# 395_Smartwatch.net
KiCad netlist of a schematic drawn in EAGLE
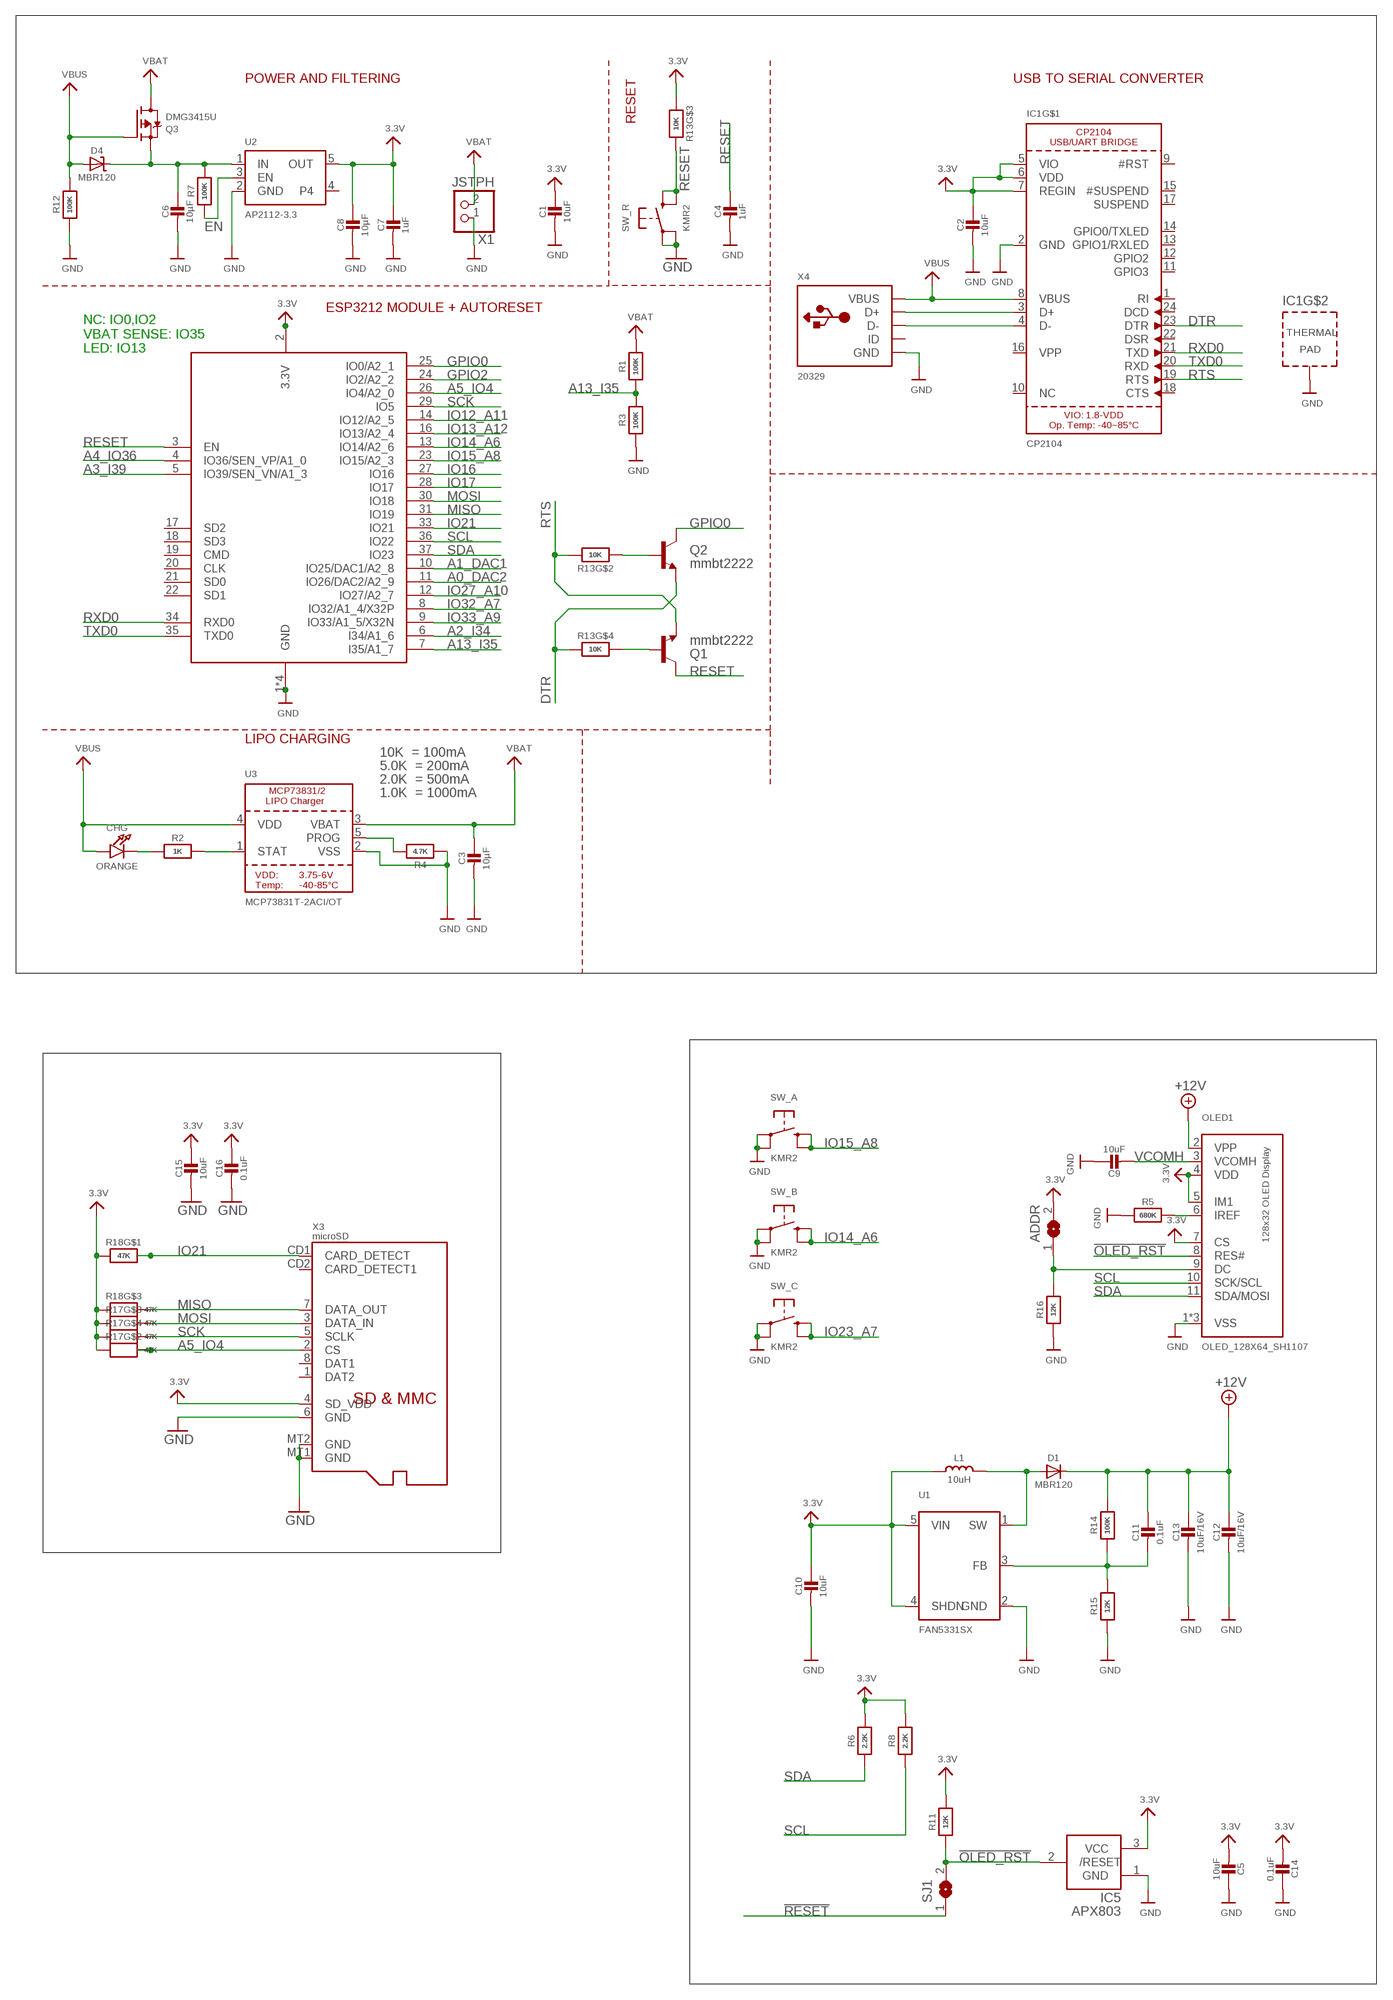
[diagram p0: schematic, sheet 1]

(export (version "E")
  (design (tool "Eeschema 10.0.6"))
  (components
    (comp (ref "ADDR")
      (value "SOLDERJUMPER")
      (footprint "eagle-import:SOLDERJUMPER_ARROW_NOPASTE")
      (libsource (lib "eagle-import") (part "SOLDERJUMPER"))
    )
    (comp (ref "C1")
      (value "10uF")
      (footprint "eagle-import:0805-NO")
      (libsource (lib "eagle-import") (part "CAP_CERAMIC0805-NOOUTLINE"))
    )
    (comp (ref "C2")
      (value "10uF")
      (footprint "eagle-import:0805-NO")
      (libsource (lib "eagle-import") (part "CAP_CERAMIC0805-NOOUTLINE"))
    )
    (comp (ref "C3")
      (value "10µF")
      (footprint "eagle-import:0805-NO")
      (libsource (lib "eagle-import") (part "CAP_CERAMIC0805-NOOUTLINE"))
    )
    (comp (ref "C4")
      (value "1uF")
      (footprint "eagle-import:0603-NO")
      (libsource (lib "eagle-import") (part "CAP_CERAMIC0603_NO"))
    )
    (comp (ref "C5")
      (value "10uF")
      (footprint "eagle-import:0805-NO")
      (libsource (lib "eagle-import") (part "CAP_CERAMIC0805-NOOUTLINE"))
    )
    (comp (ref "C6")
      (value "10µF")
      (footprint "eagle-import:0805-NO")
      (libsource (lib "eagle-import") (part "CAP_CERAMIC0805-NOOUTLINE"))
    )
    (comp (ref "C7")
      (value "1uF")
      (footprint "eagle-import:0603-NO")
      (libsource (lib "eagle-import") (part "CAP_CERAMIC0603_NO"))
    )
    (comp (ref "C8")
      (value "10µF")
      (footprint "eagle-import:0805-NO")
      (libsource (lib "eagle-import") (part "CAP_CERAMIC0805-NOOUTLINE"))
    )
    (comp (ref "C9")
      (value "10uF")
      (footprint "eagle-import:0805-NO")
      (libsource (lib "eagle-import") (part "CAP_CERAMIC0805-NOOUTLINE"))
    )
    (comp (ref "C10")
      (value "10uF")
      (footprint "eagle-import:0805-NO")
      (libsource (lib "eagle-import") (part "CAP_CERAMIC0805-NOOUTLINE"))
    )
    (comp (ref "C11")
      (value "0.1uF")
      (footprint "eagle-import:0603-NO")
      (libsource (lib "eagle-import") (part "CAP_CERAMIC0603_NO"))
    )
    (comp (ref "C12")
      (value "10uF/16V")
      (footprint "eagle-import:0805-NO")
      (libsource (lib "eagle-import") (part "CAP_CERAMIC0805-NOOUTLINE"))
    )
    (comp (ref "C13")
      (value "10uF/16V")
      (footprint "eagle-import:0805-NO")
      (libsource (lib "eagle-import") (part "CAP_CERAMIC0805-NOOUTLINE"))
    )
    (comp (ref "C14")
      (value "0.1uF")
      (footprint "eagle-import:0603-NO")
      (libsource (lib "eagle-import") (part "CAP_CERAMIC0603_NO"))
    )
    (comp (ref "C15")
      (value "10uF")
      (footprint "eagle-import:0805-NO")
      (libsource (lib "eagle-import") (part "CAP_CERAMIC0805-NOOUTLINE"))
    )
    (comp (ref "C16")
      (value "0.1uF")
      (footprint "eagle-import:0603-NO")
      (libsource (lib "eagle-import") (part "CAP_CERAMIC0603_NO"))
    )
    (comp (ref "CHG")
      (value "ORANGE")
      (footprint "eagle-import:CHIPLED_0805_NOOUTLINE")
      (libsource (lib "eagle-import") (part "LED0805_NOOUTLINE"))
    )
    (comp (ref "D1")
      (value "MBR120")
      (footprint "eagle-import:SOD-123")
      (libsource (lib "eagle-import") (part "DIODESOD-123"))
    )
    (comp (ref "D4")
      (value "MBR120")
      (footprint "eagle-import:SOD-123")
      (libsource (lib "eagle-import") (part "DIODE-SCHOTTKYSOD-123"))
    )
    (comp (ref "IC1")
      (value "CP2104")
      (footprint "eagle-import:QFN24_4MM_SMSC")
      (libsource (lib "eagle-import") (part "CP2104"))
    )
    (comp (ref "IC5")
      (value "APX803")
      (footprint "eagle-import:SOT23")
      (libsource (lib "eagle-import") (part "AXP083-SAG"))
    )
    (comp (ref "L1")
      (value "10uH")
      (footprint "eagle-import:INDUCTOR_1007")
      (libsource (lib "eagle-import") (part "INDUCTOR"))
    )
    (comp (ref "OLED1")
      (value "OLED_128X64_SH1107")
      (footprint "eagle-import:QT1107P11A")
      (libsource (lib "eagle-import") (part "OLED_128X64_SH1107"))
    )
    (comp (ref "Q1")
      (value "mmbt2222")
      (footprint "eagle-import:SOT23-3")
      (libsource (lib "eagle-import") (part "TRANSISTOR_NPNSOT23-3"))
    )
    (comp (ref "Q2")
      (value "mmbt2222")
      (footprint "eagle-import:SOT23-3")
      (libsource (lib "eagle-import") (part "TRANSISTOR_NPNSOT23-3"))
    )
    (comp (ref "Q3")
      (value "DMG3415U")
      (footprint "eagle-import:SOT23-R")
      (libsource (lib "eagle-import") (part "MOSFET-P"))
    )
    (comp (ref "R1")
      (value "100K")
      (footprint "eagle-import:0603-NO")
      (libsource (lib "eagle-import") (part "RESISTOR_0603_NOOUT"))
    )
    (comp (ref "R2")
      (value "1K")
      (footprint "eagle-import:0603-NO")
      (libsource (lib "eagle-import") (part "RESISTOR_0603_NOOUT"))
    )
    (comp (ref "R3")
      (value "100K")
      (footprint "eagle-import:0603-NO")
      (libsource (lib "eagle-import") (part "RESISTOR_0603_NOOUT"))
    )
    (comp (ref "R4")
      (value "4.7K")
      (footprint "eagle-import:0603-NO")
      (libsource (lib "eagle-import") (part "RESISTOR_0603_NOOUT"))
    )
    (comp (ref "R5")
      (value "680K")
      (footprint "eagle-import:0603-NO")
      (libsource (lib "eagle-import") (part "RESISTOR_0603_NOOUT"))
    )
    (comp (ref "R6")
      (value "2.2K")
      (footprint "eagle-import:0603-NO")
      (libsource (lib "eagle-import") (part "RESISTOR_0603_NOOUT"))
    )
    (comp (ref "R7")
      (value "100K")
      (footprint "eagle-import:0603-NO")
      (libsource (lib "eagle-import") (part "RESISTOR_0603_NOOUT"))
    )
    (comp (ref "R8")
      (value "2.2K")
      (footprint "eagle-import:0603-NO")
      (libsource (lib "eagle-import") (part "RESISTOR_0603_NOOUT"))
    )
    (comp (ref "R11")
      (value "12K")
      (footprint "eagle-import:0603-NO")
      (libsource (lib "eagle-import") (part "RESISTOR_0603_NOOUT"))
    )
    (comp (ref "R12")
      (value "100K")
      (footprint "eagle-import:0603-NO")
      (libsource (lib "eagle-import") (part "RESISTOR_0603_NOOUT"))
    )
    (comp (ref "R13")
      (value "10K")
      (footprint "eagle-import:RESPACK_4X0603")
      (libsource (lib "eagle-import") (part "RESISTOR_4PACK"))
    )
    (comp (ref "R14")
      (value "100K")
      (footprint "eagle-import:0603-NO")
      (libsource (lib "eagle-import") (part "RESISTOR_0603_NOOUT"))
    )
    (comp (ref "R15")
      (value "12K")
      (footprint "eagle-import:0603-NO")
      (libsource (lib "eagle-import") (part "RESISTOR_0603_NOOUT"))
    )
    (comp (ref "R16")
      (value "12K")
      (footprint "eagle-import:0603-NO")
      (libsource (lib "eagle-import") (part "RESISTOR_0603_NOOUT"))
    )
    (comp (ref "R17")
      (value "47K")
      (footprint "eagle-import:RESPACK_4X0603")
      (libsource (lib "eagle-import") (part "RESISTOR_4PACK"))
    )
    (comp (ref "R18")
      (value "47K")
      (footprint "eagle-import:RESPACK_4X0603")
      (libsource (lib "eagle-import") (part "RESISTOR_4PACK"))
    )
    (comp (ref "SJ1")
      (value "SOLDERJUMPERCLOSED")
      (footprint "eagle-import:SOLDERJUMPER_CLOSEDWIRE")
      (libsource (lib "eagle-import") (part "SOLDERJUMPERCLOSED"))
    )
    (comp (ref "SW_A")
      (value "KMR2")
      (footprint "eagle-import:BTN_KMR2_4.6X2.8")
      (libsource (lib "eagle-import") (part "SWITCH_TACT_SMT4.6X2.8"))
    )
    (comp (ref "SW_B")
      (value "KMR2")
      (footprint "eagle-import:BTN_KMR2_4.6X2.8")
      (libsource (lib "eagle-import") (part "SWITCH_TACT_SMT4.6X2.8"))
    )
    (comp (ref "SW_C")
      (value "KMR2")
      (footprint "eagle-import:BTN_KMR2_4.6X2.8")
      (libsource (lib "eagle-import") (part "SWITCH_TACT_SMT4.6X2.8"))
    )
    (comp (ref "SW_R")
      (value "KMR2")
      (footprint "eagle-import:BTN_KMR2_4.6X2.8")
      (libsource (lib "eagle-import") (part "SWITCH_TACT_SMT4.6X2.8"))
    )
    (comp (ref "U1")
      (value "FAN5331SX")
      (footprint "eagle-import:SOT23-5")
      (libsource (lib "eagle-import") (part "VREG_FAN5331"))
    )
    (comp (ref "U2")
      (value "AP2112-3.3")
      (footprint "eagle-import:SOT23-5")
      (libsource (lib "eagle-import") (part "VREG_SOT23-5"))
    )
    (comp (ref "U3")
      (value "MCP73831T-2ACI/OT")
      (footprint "eagle-import:SOT23-5")
      (libsource (lib "eagle-import") (part "MCP73831/2"))
    )
    (comp (ref "X1")
      (value "JSTPH")
      (footprint "eagle-import:JSTPH2")
      (libsource (lib "eagle-import") (part "CON_JST_PH_2PIN"))
    )
    (comp (ref "X2")
      (value "ESP32_WROOM32_SKINNY")
      (footprint "eagle-import:WROOM32_SKINNY")
      (libsource (lib "eagle-import") (part "ESP32_WROOM32_SKINNY"))
    )
    (comp (ref "X3")
      (value "microSD")
      (footprint "eagle-import:MICROSD")
      (libsource (lib "eagle-import") (part "MICROSD"))
    )
    (comp (ref "X4")
      (value "20329")
      (footprint "eagle-import:4UCONN_20329_V2")
      (libsource (lib "eagle-import") (part "USB_MICRO_20329_V2"))
    )
  )
  (nets
    (net (code "1") (name "+12V") (class "Default")
      (node (ref "C11") (pin "1") (pinfunction "1_1") (pintype "passive"))
      (node (ref "C12") (pin "1") (pinfunction "1_1") (pintype "passive"))
      (node (ref "C13") (pin "1") (pinfunction "1_1") (pintype "passive"))
      (node (ref "D1") (pin "C") (pinfunction "C_C") (pintype "passive"))
      (node (ref "OLED1") (pin "2") (pinfunction "VPP_2") (pintype "power_in"))
      (node (ref "R14") (pin "2") (pinfunction "2_2") (pintype "passive"))
    )
    (net (code "2") (name "/A0_DAC2") (class "Default")
      (node (ref "X2") (pin "11") (pinfunction "IO26/DAC2/A2_9_11") (pintype "bidirectional"))
    )
    (net (code "3") (name "/A1_DAC1") (class "Default")
      (node (ref "X2") (pin "10") (pinfunction "IO25/DAC1/A2_8_10") (pintype "bidirectional"))
    )
    (net (code "4") (name "/A2_I34") (class "Default")
      (node (ref "X2") (pin "6") (pinfunction "I34/A1_6_6") (pintype "bidirectional"))
    )
    (net (code "5") (name "/A3_I39") (class "Default")
      (node (ref "X2") (pin "5") (pinfunction "IO39/SEN_VN/A1_3_5") (pintype "passive"))
    )
    (net (code "6") (name "/A4_IO36") (class "Default")
      (node (ref "X2") (pin "4") (pinfunction "IO36/SEN_VP/A1_0_4") (pintype "passive"))
    )
    (net (code "7") (name "/A5_IO4") (class "Default")
      (node (ref "R17") (pin "7") (pinfunction "2_7") (pintype "passive"))
      (node (ref "X2") (pin "26") (pinfunction "IO4/A2_0_26") (pintype "bidirectional"))
      (node (ref "X3") (pin "2") (pinfunction "CS_2") (pintype "input"))
    )
    (net (code "8") (name "/A13_I35") (class "Default")
      (node (ref "R1") (pin "1") (pinfunction "1_1") (pintype "passive"))
      (node (ref "R3") (pin "2") (pinfunction "2_2") (pintype "passive"))
      (node (ref "X2") (pin "7") (pinfunction "I35/A1_7_7") (pintype "bidirectional"))
    )
    (net (code "9") (name "/DTR") (class "Default")
      (node (ref "IC1") (pin "23") (pinfunction "DTR_23") (pintype "output"))
      (node (ref "Q2") (pin "2") (pinfunction "E_2") (pintype "passive"))
      (node (ref "R13") (pin "4") (pinfunction "1_4") (pintype "passive"))
    )
    (net (code "10") (name "/EN") (class "Default")
      (node (ref "R7") (pin "1") (pinfunction "1_1") (pintype "passive"))
      (node (ref "U2") (pin "3") (pinfunction "EN_3") (pintype "input"))
    )
    (net (code "11") (name "/GPIO0") (class "Default")
      (node (ref "Q2") (pin "3") (pinfunction "C_3") (pintype "passive"))
      (node (ref "X2") (pin "25") (pinfunction "IO0/A2_1_25") (pintype "bidirectional"))
    )
    (net (code "12") (name "/GPIO2") (class "Default")
      (node (ref "X2") (pin "24") (pinfunction "IO2/A2_2_24") (pintype "bidirectional"))
    )
    (net (code "13") (name "/IO12_A11") (class "Default")
      (node (ref "X2") (pin "14") (pinfunction "IO12/A2_5_14") (pintype "bidirectional"))
    )
    (net (code "14") (name "/IO13_A12") (class "Default")
      (node (ref "X2") (pin "16") (pinfunction "IO13/A2_4_16") (pintype "bidirectional"))
    )
    (net (code "15") (name "/IO14_A6") (class "Default")
      (node (ref "SW_B") (pin "B") (pinfunction "S_B") (pintype "passive"))
      (node (ref "SW_B") (pin "B'") (pinfunction "S1_B'") (pintype "passive"))
      (node (ref "X2") (pin "13") (pinfunction "IO14/A2_6_13") (pintype "bidirectional"))
    )
    (net (code "16") (name "/IO15_A8") (class "Default")
      (node (ref "SW_A") (pin "B") (pinfunction "S_B") (pintype "passive"))
      (node (ref "SW_A") (pin "B'") (pinfunction "S1_B'") (pintype "passive"))
      (node (ref "X2") (pin "23") (pinfunction "IO15/A2_3_23") (pintype "bidirectional"))
    )
    (net (code "17") (name "/IO16") (class "Default")
      (node (ref "X2") (pin "27") (pinfunction "IO16_27") (pintype "bidirectional"))
    )
    (net (code "18") (name "/IO17") (class "Default")
      (node (ref "X2") (pin "28") (pinfunction "IO17_28") (pintype "bidirectional"))
    )
    (net (code "19") (name "/IO21") (class "Default")
      (node (ref "R18") (pin "8") (pinfunction "2_8") (pintype "passive"))
      (node (ref "X2") (pin "33") (pinfunction "IO21_33") (pintype "bidirectional"))
      (node (ref "X3") (pin "CD1") (pinfunction "CARD_DETECT_CD1") (pintype "passive"))
    )
    (net (code "20") (name "/IO23_A7") (class "Default")
      (node (ref "SW_C") (pin "B") (pinfunction "S_B") (pintype "passive"))
      (node (ref "SW_C") (pin "B'") (pinfunction "S1_B'") (pintype "passive"))
    )
    (net (code "21") (name "/IO27_A10") (class "Default")
      (node (ref "X2") (pin "12") (pinfunction "IO27/A2_7_12") (pintype "bidirectional"))
    )
    (net (code "22") (name "/IO32_A7") (class "Default")
      (node (ref "X2") (pin "8") (pinfunction "IO32/A1_4/X32P_8") (pintype "bidirectional"))
    )
    (net (code "23") (name "/IO33_A9") (class "Default")
      (node (ref "X2") (pin "9") (pinfunction "IO33/A1_5/X32N_9") (pintype "bidirectional"))
    )
    (net (code "24") (name "/MISO") (class "Default")
      (node (ref "R18") (pin "6") (pinfunction "2_6") (pintype "passive"))
      (node (ref "X2") (pin "31") (pinfunction "IO19_31") (pintype "bidirectional"))
      (node (ref "X3") (pin "7") (pinfunction "DATA_OUT_7") (pintype "output"))
    )
    (net (code "25") (name "/MOSI") (class "Default")
      (node (ref "R17") (pin "6") (pinfunction "2_6") (pintype "passive"))
      (node (ref "X2") (pin "30") (pinfunction "IO18_30") (pintype "bidirectional"))
      (node (ref "X3") (pin "3") (pinfunction "DATA_IN_3") (pintype "input"))
    )
    (net (code "26") (name "/RESET") (class "Default")
      (node (ref "C4") (pin "1") (pinfunction "1_1") (pintype "passive"))
      (node (ref "Q1") (pin "3") (pinfunction "C_3") (pintype "passive"))
      (node (ref "R13") (pin "6") (pinfunction "2_6") (pintype "passive"))
      (node (ref "SW_R") (pin "B") (pinfunction "S_B") (pintype "passive"))
      (node (ref "SW_R") (pin "B'") (pinfunction "S1_B'") (pintype "passive"))
      (node (ref "X2") (pin "3") (pinfunction "EN_3") (pintype "input"))
    )
    (net (code "27") (name "/RTS") (class "Default")
      (node (ref "IC1") (pin "19") (pinfunction "RTS_19") (pintype "output"))
      (node (ref "Q1") (pin "2") (pinfunction "E_2") (pintype "passive"))
      (node (ref "R13") (pin "7") (pinfunction "2_7") (pintype "passive"))
    )
    (net (code "28") (name "/RXD0") (class "Default")
      (node (ref "IC1") (pin "21") (pinfunction "TXD_21") (pintype "output"))
      (node (ref "X2") (pin "34") (pinfunction "RXD0_34") (pintype "input"))
    )
    (net (code "29") (name "/SCK") (class "Default")
      (node (ref "R17") (pin "5") (pinfunction "2_5") (pintype "passive"))
      (node (ref "X2") (pin "29") (pinfunction "IO5_29") (pintype "bidirectional"))
      (node (ref "X3") (pin "5") (pinfunction "SCLK_5") (pintype "input"))
    )
    (net (code "30") (name "/SCL") (class "Default")
      (node (ref "OLED1") (pin "10") (pinfunction "SCK/SCL_10") (pintype "input"))
      (node (ref "R8") (pin "1") (pinfunction "1_1") (pintype "passive"))
      (node (ref "X2") (pin "36") (pinfunction "IO22_36") (pintype "bidirectional"))
    )
    (net (code "31") (name "/SDA") (class "Default")
      (node (ref "OLED1") (pin "11") (pinfunction "SDA/MOSI_11") (pintype "input"))
      (node (ref "R6") (pin "1") (pinfunction "1_1") (pintype "passive"))
      (node (ref "X2") (pin "37") (pinfunction "IO23_37") (pintype "bidirectional"))
    )
    (net (code "32") (name "/TXD0") (class "Default")
      (node (ref "IC1") (pin "20") (pinfunction "RXD_20") (pintype "input"))
      (node (ref "X2") (pin "35") (pinfunction "TXD0_35") (pintype "output"))
    )
    (net (code "33") (name "/VCOMH") (class "Default")
      (node (ref "C9") (pin "2") (pinfunction "2_2") (pintype "passive"))
      (node (ref "OLED1") (pin "3") (pinfunction "VCOMH_3") (pintype "power_in"))
    )
    (net (code "34") (name "/~{OLED_RST}") (class "Default")
      (node (ref "IC5") (pin "2") (pinfunction "/RESET_2") (pintype "output"))
      (node (ref "OLED1") (pin "8") (pinfunction "RES#_8") (pintype "input"))
      (node (ref "R11") (pin "1") (pinfunction "1_1") (pintype "passive"))
      (node (ref "SJ1") (pin "2") (pinfunction "2_2") (pintype "passive"))
    )
    (net (code "35") (name "/~{RESET}") (class "Default")
      (node (ref "SJ1") (pin "1") (pinfunction "1_1") (pintype "passive"))
    )
    (net (code "36") (name "3.3V") (class "Default")
      (node (ref "ADDR") (pin "2") (pinfunction "2_2") (pintype "passive"))
      (node (ref "C1") (pin "1") (pinfunction "1_1") (pintype "passive"))
      (node (ref "C10") (pin "1") (pinfunction "1_1") (pintype "passive"))
      (node (ref "C14") (pin "2") (pinfunction "2_2") (pintype "passive"))
      (node (ref "C15") (pin "1") (pinfunction "1_1") (pintype "passive"))
      (node (ref "C16") (pin "1") (pinfunction "1_1") (pintype "passive"))
      (node (ref "C2") (pin "1") (pinfunction "1_1") (pintype "passive"))
      (node (ref "C5") (pin "2") (pinfunction "2_2") (pintype "passive"))
      (node (ref "C7") (pin "1") (pinfunction "1_1") (pintype "passive"))
      (node (ref "C8") (pin "1") (pinfunction "1_1") (pintype "passive"))
      (node (ref "IC1") (pin "5") (pinfunction "VIO_5") (pintype "power_in"))
      (node (ref "IC1") (pin "6") (pinfunction "VDD_6") (pintype "power_in"))
      (node (ref "IC1") (pin "7") (pinfunction "REGIN_7") (pintype "power_in"))
      (node (ref "IC5") (pin "3") (pinfunction "VCC_3") (pintype "power_in"))
      (node (ref "L1") (pin "P$1") (pinfunction "1_P$1") (pintype "passive"))
      (node (ref "OLED1") (pin "4") (pinfunction "VDD_4") (pintype "power_in"))
      (node (ref "OLED1") (pin "5") (pinfunction "IM1_5") (pintype "input"))
      (node (ref "OLED1") (pin "7") (pinfunction "CS_7") (pintype "input"))
      (node (ref "R11") (pin "2") (pinfunction "2_2") (pintype "passive"))
      (node (ref "R13") (pin "3") (pinfunction "1_3") (pintype "passive"))
      (node (ref "R17") (pin "2") (pinfunction "1_2") (pintype "passive"))
      (node (ref "R17") (pin "3") (pinfunction "1_3") (pintype "passive"))
      (node (ref "R17") (pin "4") (pinfunction "1_4") (pintype "passive"))
      (node (ref "R18") (pin "1") (pinfunction "1_1") (pintype "passive"))
      (node (ref "R18") (pin "3") (pinfunction "1_3") (pintype "passive"))
      (node (ref "R6") (pin "2") (pinfunction "2_2") (pintype "passive"))
      (node (ref "R8") (pin "2") (pinfunction "2_2") (pintype "passive"))
      (node (ref "U1") (pin "4") (pinfunction "SHDN_4") (pintype "bidirectional"))
      (node (ref "U1") (pin "5") (pinfunction "VIN_5") (pintype "bidirectional"))
      (node (ref "U2") (pin "5") (pinfunction "OUT_5") (pintype "power_in"))
      (node (ref "X2") (pin "2") (pinfunction "3.3V_2") (pintype "passive"))
      (node (ref "X3") (pin "4") (pinfunction "SD_VDD_4") (pintype "power_in"))
    )
    (net (code "37") (name "GND") (class "Default")
      (node (ref "C1") (pin "2") (pinfunction "2_2") (pintype "passive"))
      (node (ref "C10") (pin "2") (pinfunction "2_2") (pintype "passive"))
      (node (ref "C12") (pin "2") (pinfunction "2_2") (pintype "passive"))
      (node (ref "C13") (pin "2") (pinfunction "2_2") (pintype "passive"))
      (node (ref "C14") (pin "1") (pinfunction "1_1") (pintype "passive"))
      (node (ref "C15") (pin "2") (pinfunction "2_2") (pintype "passive"))
      (node (ref "C16") (pin "2") (pinfunction "2_2") (pintype "passive"))
      (node (ref "C2") (pin "2") (pinfunction "2_2") (pintype "passive"))
      (node (ref "C3") (pin "2") (pinfunction "2_2") (pintype "passive"))
      (node (ref "C4") (pin "2") (pinfunction "2_2") (pintype "passive"))
      (node (ref "C5") (pin "1") (pinfunction "1_1") (pintype "passive"))
      (node (ref "C6") (pin "2") (pinfunction "2_2") (pintype "passive"))
      (node (ref "C7") (pin "2") (pinfunction "2_2") (pintype "passive"))
      (node (ref "C8") (pin "2") (pinfunction "2_2") (pintype "passive"))
      (node (ref "C9") (pin "1") (pinfunction "1_1") (pintype "passive"))
      (node (ref "IC1") (pin "2") (pinfunction "GND_2") (pintype "power_in"))
      (node (ref "IC1") (pin "THERM") (pinfunction "TP_THERM") (pintype "power_in"))
      (node (ref "IC5") (pin "1") (pinfunction "GND_1") (pintype "power_in"))
      (node (ref "OLED1") (pin "1") (pinfunction "VSS_1") (pintype "power_in"))
      (node (ref "OLED1") (pin "12") (pinfunction "VSS_12") (pintype "power_in"))
      (node (ref "OLED1") (pin "13") (pinfunction "VSS_13") (pintype "power_in"))
      (node (ref "R12") (pin "1") (pinfunction "1_1") (pintype "passive"))
      (node (ref "R15") (pin "1") (pinfunction "1_1") (pintype "passive"))
      (node (ref "R16") (pin "1") (pinfunction "1_1") (pintype "passive"))
      (node (ref "R3") (pin "1") (pinfunction "1_1") (pintype "passive"))
      (node (ref "R4") (pin "1") (pinfunction "1_1") (pintype "passive"))
      (node (ref "R5") (pin "1") (pinfunction "1_1") (pintype "passive"))
      (node (ref "SW_A") (pin "A") (pinfunction "P_A") (pintype "passive"))
      (node (ref "SW_A") (pin "A'") (pinfunction "P1_A'") (pintype "passive"))
      (node (ref "SW_B") (pin "A") (pinfunction "P_A") (pintype "passive"))
      (node (ref "SW_B") (pin "A'") (pinfunction "P1_A'") (pintype "passive"))
      (node (ref "SW_C") (pin "A") (pinfunction "P_A") (pintype "passive"))
      (node (ref "SW_C") (pin "A'") (pinfunction "P1_A'") (pintype "passive"))
      (node (ref "SW_R") (pin "A") (pinfunction "P_A") (pintype "passive"))
      (node (ref "SW_R") (pin "A'") (pinfunction "P1_A'") (pintype "passive"))
      (node (ref "U1") (pin "2") (pinfunction "GND_2") (pintype "bidirectional"))
      (node (ref "U2") (pin "2") (pinfunction "GND_2") (pintype "power_in"))
      (node (ref "U3") (pin "2") (pinfunction "VSS_2") (pintype "power_in"))
      (node (ref "X1") (pin "1") (pinfunction "1_1") (pintype "passive"))
      (node (ref "X2") (pin "1") (pinfunction "GND_1") (pintype "passive"))
      (node (ref "X2") (pin "15") (pinfunction "GND_15") (pintype "passive"))
      (node (ref "X2") (pin "38") (pinfunction "GND_38") (pintype "passive"))
      (node (ref "X2") (pin "P$1") (pinfunction "GND_P$1") (pintype "passive"))
      (node (ref "X3") (pin "6") (pinfunction "GND_6") (pintype "power_in"))
      (node (ref "X3") (pin "MT1") (pinfunction "GND_MT1") (pintype "power_in"))
      (node (ref "X3") (pin "MT2") (pinfunction "GND_MT2") (pintype "power_in"))
      (node (ref "X4") (pin "BASE@1") (pinfunction "GND_BASE@1") (pintype "power_in"))
      (node (ref "X4") (pin "BASE@2") (pinfunction "GND_BASE@2") (pintype "power_in"))
      (node (ref "X4") (pin "GND") (pinfunction "GND_GND") (pintype "power_in"))
      (node (ref "X4") (pin "SPRT@1") (pinfunction "GND_SPRT@1") (pintype "power_in"))
      (node (ref "X4") (pin "SPRT@2") (pinfunction "GND_SPRT@2") (pintype "power_in"))
      (node (ref "X4") (pin "SPRT@3") (pinfunction "GND_SPRT@3") (pintype "power_in"))
      (node (ref "X4") (pin "SPRT@4") (pinfunction "GND_SPRT@4") (pintype "power_in"))
    )
    (net (code "38") (name "Net-(CHG-PadC)") (class "Default")
      (node (ref "CHG") (pin "C") (pinfunction "C_C") (pintype "passive"))
      (node (ref "R2") (pin "1") (pinfunction "1_1") (pintype "passive"))
    )
    (net (code "39") (name "Net-(IC1A-D+)") (class "Default")
      (node (ref "IC1") (pin "3") (pinfunction "D+_3") (pintype "bidirectional"))
      (node (ref "X4") (pin "D+") (pinfunction "D+_D+") (pintype "bidirectional"))
    )
    (net (code "40") (name "Net-(IC1A-D-)") (class "Default")
      (node (ref "IC1") (pin "4") (pinfunction "D-_4") (pintype "bidirectional"))
      (node (ref "X4") (pin "D-") (pinfunction "D-_D-") (pintype "bidirectional"))
    )
    (net (code "41") (name "Net-(L1-2)") (class "Default")
      (node (ref "D1") (pin "A") (pinfunction "A_A") (pintype "passive"))
      (node (ref "L1") (pin "P$2") (pinfunction "2_P$2") (pintype "passive"))
      (node (ref "U1") (pin "1") (pinfunction "SW_1") (pintype "bidirectional"))
    )
    (net (code "42") (name "Net-(OLED1-DC)") (class "Default")
      (node (ref "ADDR") (pin "1") (pinfunction "1_1") (pintype "passive"))
      (node (ref "OLED1") (pin "9") (pinfunction "DC_9") (pintype "input"))
      (node (ref "R16") (pin "2") (pinfunction "2_2") (pintype "passive"))
    )
    (net (code "43") (name "Net-(OLED1-IREF)") (class "Default")
      (node (ref "OLED1") (pin "6") (pinfunction "IREF_6") (pintype "bidirectional"))
      (node (ref "R5") (pin "2") (pinfunction "2_2") (pintype "passive"))
    )
    (net (code "44") (name "Net-(Q1-B)") (class "Default")
      (node (ref "Q1") (pin "1") (pinfunction "B_1") (pintype "passive"))
      (node (ref "R13") (pin "5") (pinfunction "2_5") (pintype "passive"))
    )
    (net (code "45") (name "Net-(Q2-B)") (class "Default")
      (node (ref "Q2") (pin "1") (pinfunction "B_1") (pintype "passive"))
      (node (ref "R13") (pin "2") (pinfunction "1_2") (pintype "passive"))
    )
    (net (code "46") (name "Net-(Q3-S)") (class "Default")
      (node (ref "C6") (pin "1") (pinfunction "1_1") (pintype "passive"))
      (node (ref "D4") (pin "C") (pinfunction "C_C") (pintype "passive"))
      (node (ref "Q3") (pin "2") (pinfunction "S_2") (pintype "passive"))
      (node (ref "R7") (pin "2") (pinfunction "2_2") (pintype "passive"))
      (node (ref "U2") (pin "1") (pinfunction "IN_1") (pintype "power_in"))
    )
    (net (code "47") (name "Net-(U1-FB)") (class "Default")
      (node (ref "C11") (pin "2") (pinfunction "2_2") (pintype "passive"))
      (node (ref "R14") (pin "1") (pinfunction "1_1") (pintype "passive"))
      (node (ref "R15") (pin "2") (pinfunction "2_2") (pintype "passive"))
      (node (ref "U1") (pin "3") (pinfunction "FB_3") (pintype "bidirectional"))
    )
    (net (code "48") (name "Net-(U3-PROG)") (class "Default")
      (node (ref "R4") (pin "2") (pinfunction "2_2") (pintype "passive"))
      (node (ref "U3") (pin "5") (pinfunction "PROG_5") (pintype "input"))
    )
    (net (code "49") (name "Net-(U3-STAT)") (class "Default")
      (node (ref "R2") (pin "2") (pinfunction "2_2") (pintype "passive"))
      (node (ref "U3") (pin "1") (pinfunction "STAT_1") (pintype "output"))
    )
    (net (code "50") (name "VBAT") (class "Default")
      (node (ref "C3") (pin "1") (pinfunction "1_1") (pintype "passive"))
      (node (ref "Q3") (pin "3") (pinfunction "D_3") (pintype "passive"))
      (node (ref "R1") (pin "2") (pinfunction "2_2") (pintype "passive"))
      (node (ref "U3") (pin "3") (pinfunction "VBAT_3") (pintype "power_in"))
      (node (ref "X1") (pin "2") (pinfunction "2_2") (pintype "passive"))
    )
    (net (code "51") (name "VBUS") (class "Default")
      (node (ref "CHG") (pin "A") (pinfunction "A_A") (pintype "passive"))
      (node (ref "D4") (pin "A") (pinfunction "A_A") (pintype "passive"))
      (node (ref "IC1") (pin "8") (pinfunction "VBUS_8") (pintype "power_in"))
      (node (ref "Q3") (pin "1") (pinfunction "G_1") (pintype "passive"))
      (node (ref "R12") (pin "2") (pinfunction "2_2") (pintype "passive"))
      (node (ref "U3") (pin "4") (pinfunction "VDD_4") (pintype "power_in"))
      (node (ref "X4") (pin "VBUS") (pinfunction "VBUS_VBUS") (pintype "power_in"))
    )
    (net (code "52") (name "unconnected-(IC1A-#RST-Pad9)") (class "Default")
      (node (ref "IC1") (pin "9") (pinfunction "#RST_9") (pintype "bidirectional"))
    )
    (net (code "53") (name "unconnected-(IC1A-#SUSPEND-Pad15)") (class "Default")
      (node (ref "IC1") (pin "15") (pinfunction "#SUSPEND_15") (pintype "output"))
    )
    (net (code "54") (name "unconnected-(IC1A-CTS-Pad18)") (class "Default")
      (node (ref "IC1") (pin "18") (pinfunction "CTS_18") (pintype "input"))
    )
    (net (code "55") (name "unconnected-(IC1A-DCD-Pad24)") (class "Default")
      (node (ref "IC1") (pin "24") (pinfunction "DCD_24") (pintype "input"))
    )
    (net (code "56") (name "unconnected-(IC1A-DSR-Pad22)") (class "Default")
      (node (ref "IC1") (pin "22") (pinfunction "DSR_22") (pintype "input"))
    )
    (net (code "57") (name "unconnected-(IC1A-GPIO0{slash}TXLED-Pad14)") (class "Default")
      (node (ref "IC1") (pin "14") (pinfunction "GPIO0/TXLED_14") (pintype "bidirectional"))
    )
    (net (code "58") (name "unconnected-(IC1A-GPIO1{slash}RXLED-Pad13)") (class "Default")
      (node (ref "IC1") (pin "13") (pinfunction "GPIO1/RXLED_13") (pintype "bidirectional"))
    )
    (net (code "59") (name "unconnected-(IC1A-GPIO2-Pad12)") (class "Default")
      (node (ref "IC1") (pin "12") (pinfunction "GPIO2_12") (pintype "bidirectional"))
    )
    (net (code "60") (name "unconnected-(IC1A-GPIO3-Pad11)") (class "Default")
      (node (ref "IC1") (pin "11") (pinfunction "GPIO3_11") (pintype "bidirectional"))
    )
    (net (code "61") (name "unconnected-(IC1A-NC-Pad10)") (class "Default")
      (node (ref "IC1") (pin "10") (pinfunction "NC_10") (pintype "no_connect"))
    )
    (net (code "62") (name "unconnected-(IC1A-RI-Pad1)") (class "Default")
      (node (ref "IC1") (pin "1") (pinfunction "RI_1") (pintype "input"))
    )
    (net (code "63") (name "unconnected-(IC1A-SUSPEND-Pad17)") (class "Default")
      (node (ref "IC1") (pin "17") (pinfunction "SUSPEND_17") (pintype "output"))
    )
    (net (code "64") (name "unconnected-(IC1A-VPP-Pad16)") (class "Default")
      (node (ref "IC1") (pin "16") (pinfunction "VPP_16") (pintype "bidirectional"))
    )
    (net (code "65") (name "unconnected-(U2-P4-Pad4)") (class "Default")
      (node (ref "U2") (pin "4") (pinfunction "P4_4") (pintype "bidirectional"))
    )
    (net (code "66") (name "unconnected-(X2-CLK-Pad20)") (class "Default")
      (node (ref "X2") (pin "20") (pinfunction "CLK_20") (pintype "bidirectional"))
    )
    (net (code "67") (name "unconnected-(X2-CMD-Pad19)") (class "Default")
      (node (ref "X2") (pin "19") (pinfunction "CMD_19") (pintype "bidirectional"))
    )
    (net (code "68") (name "unconnected-(X2-SD0-Pad21)") (class "Default")
      (node (ref "X2") (pin "21") (pinfunction "SD0_21") (pintype "bidirectional"))
    )
    (net (code "69") (name "unconnected-(X2-SD1-Pad22)") (class "Default")
      (node (ref "X2") (pin "22") (pinfunction "SD1_22") (pintype "bidirectional"))
    )
    (net (code "70") (name "unconnected-(X2-SD2-Pad17)") (class "Default")
      (node (ref "X2") (pin "17") (pinfunction "SD2_17") (pintype "bidirectional"))
    )
    (net (code "71") (name "unconnected-(X2-SD3-Pad18)") (class "Default")
      (node (ref "X2") (pin "18") (pinfunction "SD3_18") (pintype "bidirectional"))
    )
    (net (code "72") (name "unconnected-(X3-CARD_DETECT1-PadCD2)") (class "Default")
      (node (ref "X3") (pin "CD2") (pinfunction "CARD_DETECT1_CD2") (pintype "passive"))
    )
    (net (code "73") (name "unconnected-(X3-DAT1-Pad8)") (class "Default")
      (node (ref "X3") (pin "8") (pinfunction "DAT1_8") (pintype "bidirectional"))
    )
    (net (code "74") (name "unconnected-(X3-DAT2-Pad1)") (class "Default")
      (node (ref "X3") (pin "1") (pinfunction "DAT2_1") (pintype "bidirectional"))
    )
    (net (code "75") (name "unconnected-(X4-PadID)") (class "Default")
      (node (ref "X4") (pin "ID") (pinfunction "ID_ID") (pintype "bidirectional"))
    )
  )
)
